# Power.net
KiCad netlist of a schematic drawn in Altium Designer
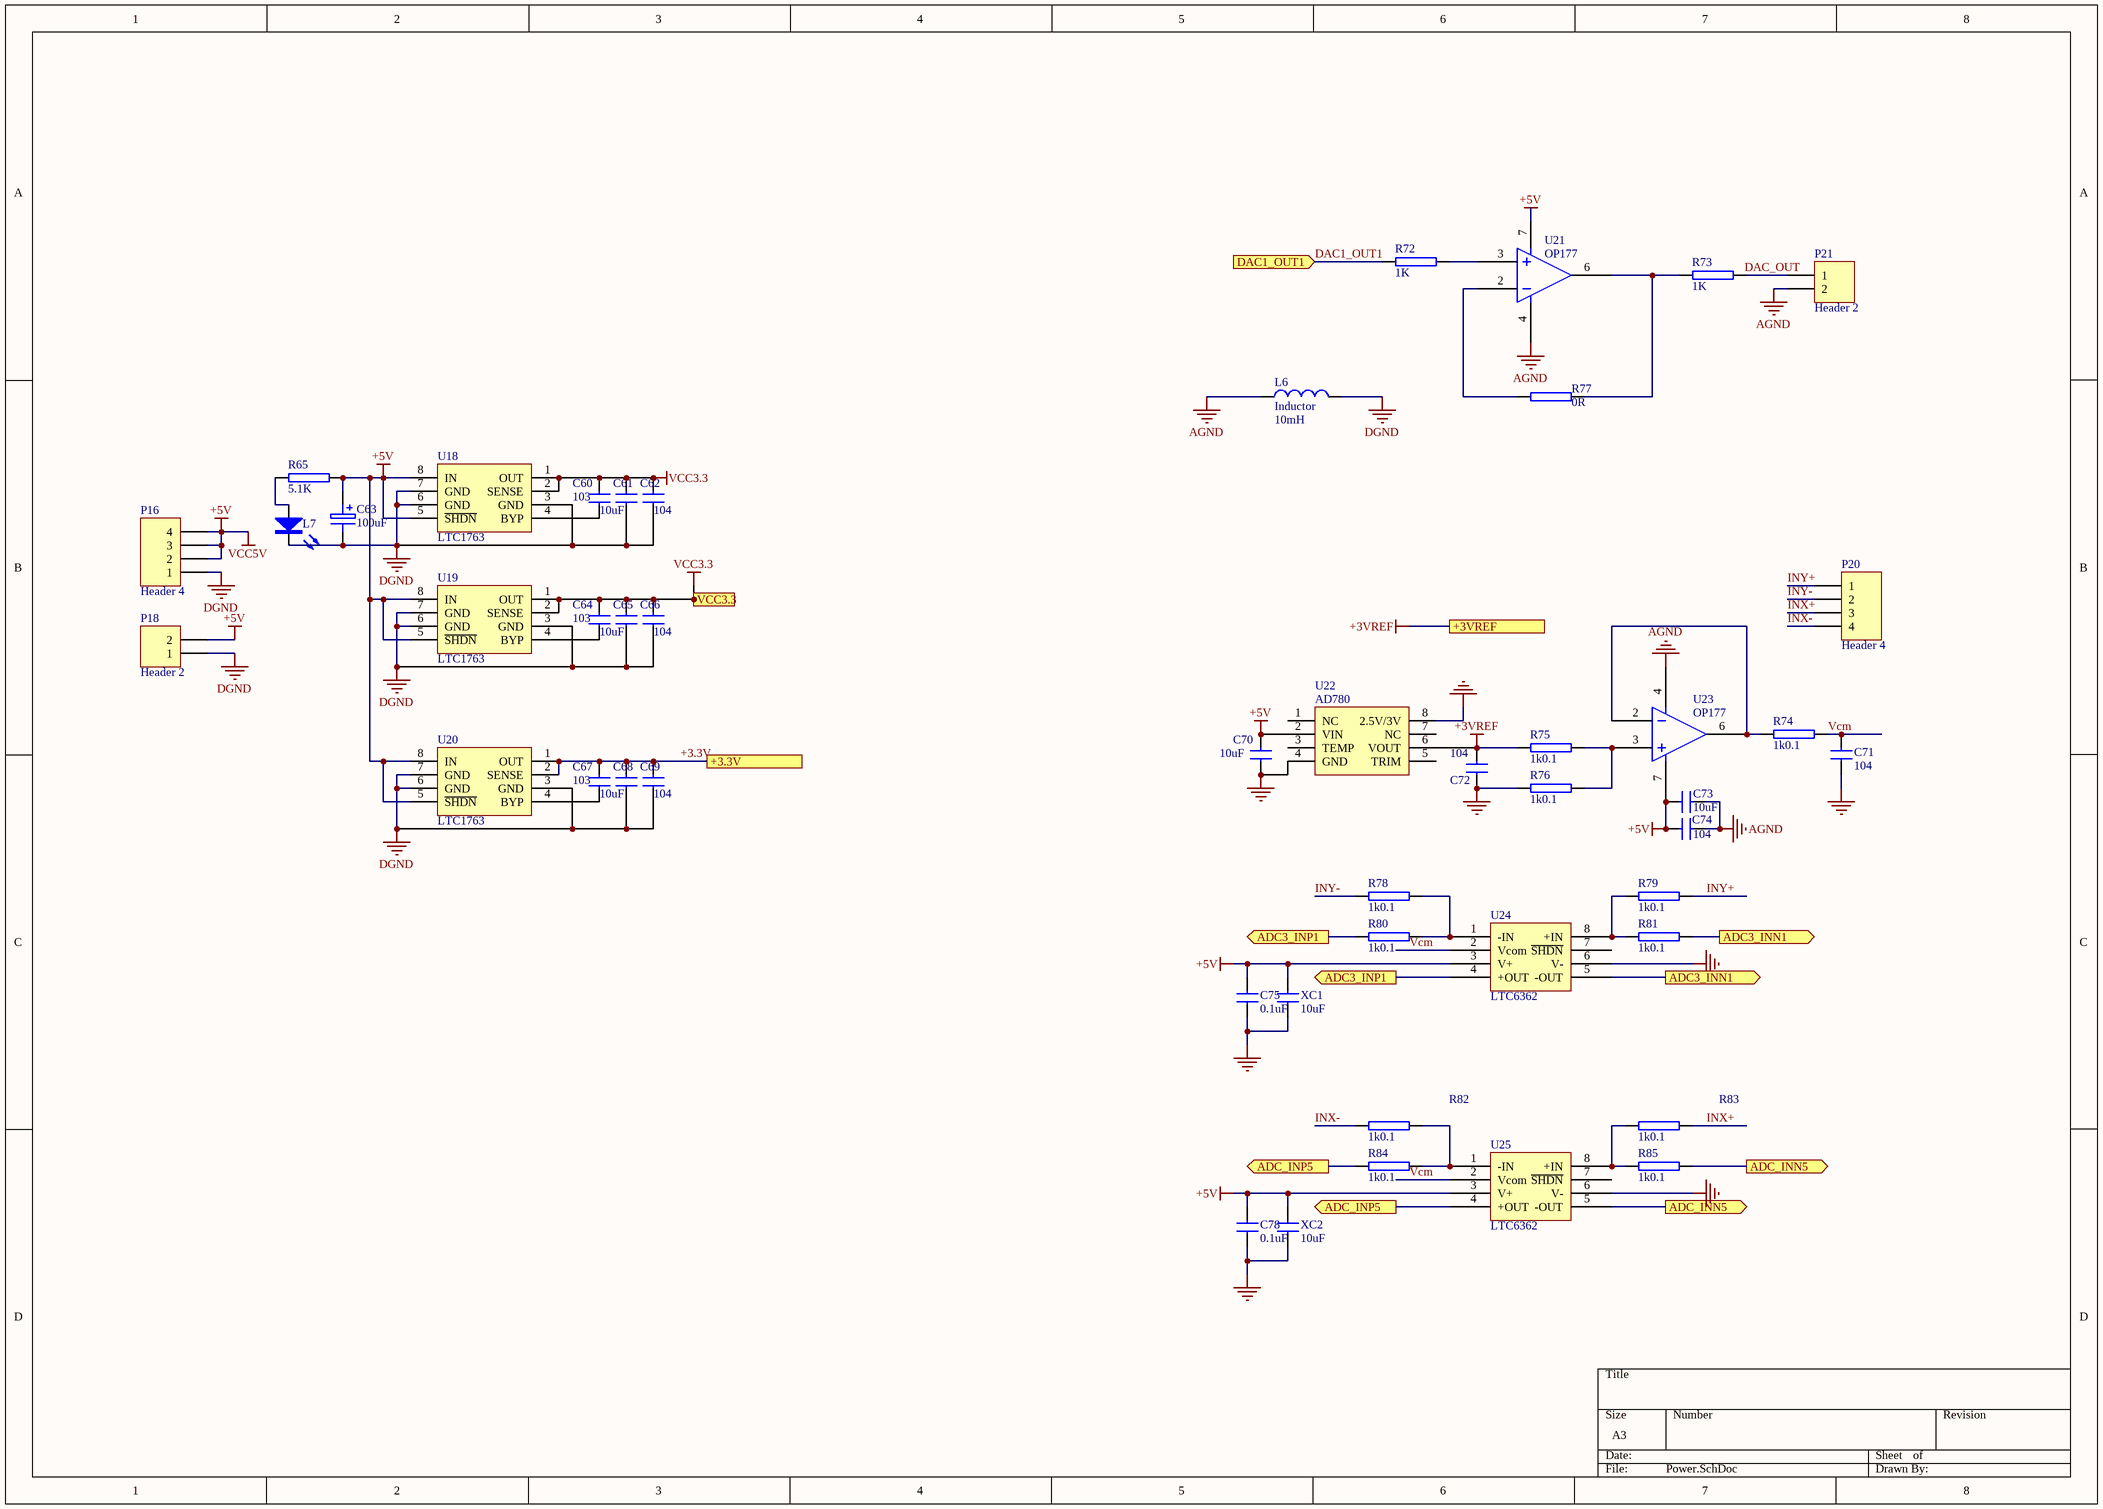
[diagram p0: Power.SchDoc]

(export (version "E")
  (design (tool "Eeschema 10.0.6"))
  (components
    (comp (ref "C60") (value "103") (footprint "0603") (libsource (lib "电容") (part "C")))
    (comp (ref "C61") (value "10uF") (footprint "0603") (libsource (lib "电容") (part "C")))
    (comp (ref "C62") (value "104") (footprint "0603") (libsource (lib "电容") (part "C")))
    (comp (ref "C63") (value "100uF") (footprint "100UF/25V_CA") (libsource (lib "电容") (part "ELECTRO1")))
    (comp (ref "C64") (value "103") (footprint "0603") (libsource (lib "电容") (part "C")))
    (comp (ref "C65") (value "10uF") (footprint "0603") (libsource (lib "电容") (part "C")))
    (comp (ref "C66") (value "104") (footprint "0603") (libsource (lib "电容") (part "C")))
    (comp (ref "C67") (value "103") (footprint "0603") (libsource (lib "电容") (part "C")))
    (comp (ref "C68") (value "10uF") (footprint "0603") (libsource (lib "电容") (part "C")))
    (comp (ref "C69") (value "104") (footprint "0603") (libsource (lib "电容") (part "C")))
    (comp (ref "C70") (value "10uF") (footprint "0603") (libsource (lib "*") (part "C")))
    (comp (ref "C71") (value "104") (footprint "0603") (libsource (lib "电容") (part "C")))
    (comp (ref "C72") (value "104") (footprint "0603") (libsource (lib "*") (part "C")))
    (comp (ref "C73") (value "10uF") (footprint "0603") (libsource (lib "电容") (part "C")))
    (comp (ref "C74") (value "104") (footprint "0603") (libsource (lib "电容") (part "C")))
    (comp (ref "C75") (value "0.1uF") (footprint "0603") (libsource (lib "电容") (part "C")))
    (comp (ref "C78") (value "0.1uF") (footprint "0603") (libsource (lib "电容") (part "C")))
    (comp (ref "L6")
      (value "Inductor")
      (footprint "0805")
      (fields (field (name "ALTIUM_VALUE") "10mH") (field (name "PUBLISHER") "Altium Limited"))
      (libsource (lib "Miscellaneous Devices") (part "Inductor"))
    )
    (comp (ref "L7") (value "LED") (footprint "0805LED") (libsource (lib "二极管") (part "LED")))
    (comp (ref "P16")
      (value "Header 4")
      (footprint "HDR1X4")
      (description "Header, 4-Pin")
      (fields (field (name "PUBLISHER") "Altium Limited"))
      (libsource (lib "") (part "Header 4_1"))
    )
    (comp (ref "P18")
      (value "Header 2")
      (footprint "HDR1X2")
      (description "Header, 2-Pin")
      (fields (field (name "PUBLISHER") "Altium Limited"))
      (libsource (lib "") (part "Header 2_1"))
    )
    (comp (ref "P20")
      (value "Header 4")
      (footprint "HDR1X4")
      (description "Header, 4-Pin")
      (fields (field (name "PUBLISHER") "Altium Limited"))
      (libsource (lib "Miscellaneous Connectors") (part "Header 4"))
    )
    (comp (ref "P21")
      (value "Header 2")
      (footprint "HDR1X2")
      (description "Header, 2-Pin")
      (fields (field (name "PUBLISHER") "Altium Limited"))
      (libsource (lib "Miscellaneous Connectors") (part "Header 2"))
    )
    (comp (ref "R65") (value "5.1K") (footprint "0603") (libsource (lib "电阻") (part "RES")))
    (comp (ref "R72") (value "1K") (footprint "0603") (libsource (lib "电阻") (part "RES")))
    (comp (ref "R73") (value "1K") (footprint "0603") (libsource (lib "电阻") (part "RES")))
    (comp (ref "R74") (value "1k0.1") (footprint "0603") (libsource (lib "电阻") (part "RES")))
    (comp (ref "R75") (value "1k0.1") (footprint "0603") (libsource (lib "电阻") (part "RES")))
    (comp (ref "R76") (value "1k0.1") (footprint "0603") (libsource (lib "电阻") (part "RES")))
    (comp (ref "R77") (value "0R") (footprint "0603") (libsource (lib "电阻") (part "RES")))
    (comp (ref "R78") (value "1k0.1") (footprint "0603") (libsource (lib "电阻") (part "RES")))
    (comp (ref "R79") (value "1k0.1") (footprint "0603") (libsource (lib "电阻") (part "RES")))
    (comp (ref "R80") (value "1k0.1") (footprint "0603") (libsource (lib "电阻") (part "RES")))
    (comp (ref "R81") (value "1k0.1") (footprint "0603") (libsource (lib "电阻") (part "RES")))
    (comp (ref "R82") (value "1k0.1") (footprint "0603") (libsource (lib "电阻") (part "RES")))
    (comp (ref "R83") (value "1k0.1") (footprint "0603") (libsource (lib "电阻") (part "RES")))
    (comp (ref "R84") (value "1k0.1") (footprint "0603") (libsource (lib "电阻") (part "RES")))
    (comp (ref "R85") (value "1k0.1") (footprint "0603") (libsource (lib "电阻") (part "RES")))
    (comp (ref "U18") (value "LTC1763") (footprint "SO-8") (libsource (lib "单片机") (part "LT1763")))
    (comp (ref "U19") (value "LTC1763") (footprint "SO-8") (libsource (lib "单片机") (part "LT1763")))
    (comp (ref "U20") (value "LTC1763") (footprint "SO-8") (libsource (lib "单片机") (part "LT1763")))
    (comp (ref "U21") (value "OP177") (footprint "SO-8") (libsource (lib "*") (part "LM207")))
    (comp (ref "U22") (value "AD780") (footprint "SO-8") (libsource (lib "*") (part "AD780")))
    (comp (ref "U23") (value "OP177") (footprint "SO-8") (libsource (lib "*") (part "LM207")))
    (comp (ref "U24")
      (value "LTC6362")
      (footprint "LT6350XIN")
      (description "SAR ADC Drive")
      (libsource (lib "ADorADC") (part "LTC6362"))
    )
    (comp (ref "U25")
      (value "LTC6362")
      (footprint "LT6350XIN")
      (description "SAR ADC Drive")
      (libsource (lib "ADorADC") (part "LTC6362"))
    )
    (comp (ref "XC1") (value "10uF") (footprint "0603") (libsource (lib "电容") (part "C")))
    (comp (ref "XC2") (value "10uF") (footprint "0603") (libsource (lib "电容") (part "C")))
  )
  (nets
    (net (code "1") (name "+3VREF") (class "Default")
      (node (ref "C72") (pin "2") (pinfunction "2_2") (pintype "passive"))
      (node (ref "R75") (pin "1") (pinfunction "1_1") (pintype "passive"))
      (node (ref "U22") (pin "6") (pinfunction "VOUT_6") (pintype "passive"))
    )
    (net (code "2") (name "+5V") (class "Default")
      (node (ref "C63") (pin "1") (pintype "passive"))
      (node (ref "C70") (pin "1") (pinfunction "1_1") (pintype "passive"))
      (node (ref "C73") (pin "2") (pinfunction "2_2") (pintype "passive"))
      (node (ref "C74") (pin "2") (pinfunction "2_2") (pintype "passive"))
      (node (ref "C75") (pin "2") (pinfunction "2_2") (pintype "passive"))
      (node (ref "C78") (pin "2") (pinfunction "2_2") (pintype "passive"))
      (node (ref "P16") (pin "2") (pinfunction "2_2") (pintype "passive"))
      (node (ref "P16") (pin "3") (pinfunction "3_3") (pintype "passive"))
      (node (ref "P16") (pin "4") (pinfunction "4_4") (pintype "passive"))
      (node (ref "P18") (pin "2") (pinfunction "2_2") (pintype "passive"))
      (node (ref "R65") (pin "1") (pinfunction "1_1") (pintype "passive"))
      (node (ref "U18") (pin "5") (pinfunction "~{SHDN}_5") (pintype "passive"))
      (node (ref "U18") (pin "8") (pinfunction "IN_8") (pintype "passive"))
      (node (ref "U19") (pin "5") (pinfunction "~{SHDN}_5") (pintype "passive"))
      (node (ref "U19") (pin "8") (pinfunction "IN_8") (pintype "passive"))
      (node (ref "U20") (pin "5") (pinfunction "~{SHDN}_5") (pintype "passive"))
      (node (ref "U20") (pin "8") (pinfunction "IN_8") (pintype "passive"))
      (node (ref "U21") (pin "7") (pintype "passive"))
      (node (ref "U22") (pin "2") (pinfunction "VIN_2") (pintype "passive"))
      (node (ref "U23") (pin "7") (pintype "passive"))
      (node (ref "U24") (pin "3") (pinfunction "V+_3") (pintype "passive"))
      (node (ref "U25") (pin "3") (pinfunction "V+_3") (pintype "passive"))
      (node (ref "XC1") (pin "1") (pinfunction "1_1") (pintype "passive"))
      (node (ref "XC2") (pin "1") (pinfunction "1_1") (pintype "passive"))
    )
    (net (code "3") (name "/+3.3V") (class "Default")
      (node (ref "C67") (pin "1") (pinfunction "1_1") (pintype "passive"))
      (node (ref "C68") (pin "1") (pinfunction "1_1") (pintype "passive"))
      (node (ref "C69") (pin "1") (pinfunction "1_1") (pintype "passive"))
      (node (ref "U20") (pin "1") (pinfunction "OUT_1") (pintype "passive"))
      (node (ref "U20") (pin "2") (pinfunction "SENSE_2") (pintype "passive"))
    )
    (net (code "4") (name "/ADC3_INN1") (class "Default")
      (node (ref "R81") (pin "2") (pinfunction "2_2") (pintype "passive"))
      (node (ref "U24") (pin "5") (pinfunction "-OUT_5") (pintype "passive"))
    )
    (net (code "5") (name "/ADC3_INP1") (class "Default")
      (node (ref "R80") (pin "1") (pinfunction "1_1") (pintype "passive"))
      (node (ref "U24") (pin "4") (pinfunction "+OUT_4") (pintype "passive"))
    )
    (net (code "6") (name "/ADC_INN5") (class "Default")
      (node (ref "R85") (pin "2") (pinfunction "2_2") (pintype "passive"))
      (node (ref "U25") (pin "5") (pinfunction "-OUT_5") (pintype "passive"))
    )
    (net (code "7") (name "/ADC_INP5") (class "Default")
      (node (ref "R84") (pin "1") (pinfunction "1_1") (pintype "passive"))
      (node (ref "U25") (pin "4") (pinfunction "+OUT_4") (pintype "passive"))
    )
    (net (code "8") (name "/DAC1_OUT1") (class "Default")
      (node (ref "R72") (pin "2") (pinfunction "2_2") (pintype "passive"))
    )
    (net (code "10") (name "/INX+") (class "Default")
      (node (ref "P20") (pin "3") (pinfunction "3_3") (pintype "passive"))
      (node (ref "R83") (pin "2") (pinfunction "2_2") (pintype "passive"))
    )
    (net (code "11") (name "/INX-") (class "Default")
      (node (ref "P20") (pin "4") (pinfunction "4_4") (pintype "passive"))
      (node (ref "R82") (pin "2") (pinfunction "2_2") (pintype "passive"))
    )
    (net (code "12") (name "/INY+") (class "Default")
      (node (ref "P20") (pin "1") (pinfunction "1_1") (pintype "passive"))
      (node (ref "R79") (pin "2") (pinfunction "2_2") (pintype "passive"))
    )
    (net (code "13") (name "/INY-") (class "Default")
      (node (ref "P20") (pin "2") (pinfunction "2_2") (pintype "passive"))
      (node (ref "R78") (pin "2") (pinfunction "2_2") (pintype "passive"))
    )
    (net (code "14") (name "/Vcm") (class "Default")
      (node (ref "C71") (pin "1") (pinfunction "1_1") (pintype "passive"))
      (node (ref "R74") (pin "2") (pinfunction "2_2") (pintype "passive"))
      (node (ref "U24") (pin "2") (pinfunction "Vcom_2") (pintype "passive"))
      (node (ref "U25") (pin "2") (pinfunction "Vcom_2") (pintype "passive"))
    )
    (net (code "15") (name "AGND") (class "Default")
      (node (ref "C70") (pin "2") (pinfunction "2_2") (pintype "passive"))
      (node (ref "C71") (pin "2") (pinfunction "2_2") (pintype "passive"))
      (node (ref "C72") (pin "1") (pinfunction "1_1") (pintype "passive"))
      (node (ref "C73") (pin "1") (pinfunction "1_1") (pintype "passive"))
      (node (ref "C74") (pin "1") (pinfunction "1_1") (pintype "passive"))
      (node (ref "C75") (pin "1") (pinfunction "1_1") (pintype "passive"))
      (node (ref "C78") (pin "1") (pinfunction "1_1") (pintype "passive"))
      (node (ref "L6") (pin "1") (pinfunction "1_1") (pintype "passive"))
      (node (ref "P21") (pin "2") (pinfunction "2_2") (pintype "passive"))
      (node (ref "R76") (pin "1") (pinfunction "1_1") (pintype "passive"))
      (node (ref "U21") (pin "4") (pintype "passive"))
      (node (ref "U22") (pin "4") (pinfunction "GND_4") (pintype "passive"))
      (node (ref "U22") (pin "8") (pinfunction "2.5V/3V_8") (pintype "passive"))
      (node (ref "U23") (pin "4") (pintype "passive"))
      (node (ref "U24") (pin "6") (pinfunction "V-_6") (pintype "passive"))
      (node (ref "U25") (pin "6") (pinfunction "V-_6") (pintype "passive"))
      (node (ref "XC1") (pin "2") (pinfunction "2_2") (pintype "passive"))
      (node (ref "XC2") (pin "2") (pinfunction "2_2") (pintype "passive"))
    )
    (net (code "16") (name "DGND") (class "Default")
      (node (ref "C61") (pin "2") (pinfunction "2_2") (pintype "passive"))
      (node (ref "C62") (pin "2") (pinfunction "2_2") (pintype "passive"))
      (node (ref "C63") (pin "2") (pintype "passive"))
      (node (ref "C65") (pin "2") (pinfunction "2_2") (pintype "passive"))
      (node (ref "C66") (pin "2") (pinfunction "2_2") (pintype "passive"))
      (node (ref "C68") (pin "2") (pinfunction "2_2") (pintype "passive"))
      (node (ref "C69") (pin "2") (pinfunction "2_2") (pintype "passive"))
      (node (ref "L6") (pin "2") (pinfunction "2_2") (pintype "passive"))
      (node (ref "L7") (pin "2") (pinfunction "K_2") (pintype "passive"))
      (node (ref "P16") (pin "1") (pinfunction "1_1") (pintype "passive"))
      (node (ref "P18") (pin "1") (pinfunction "1_1") (pintype "passive"))
      (node (ref "U18") (pin "3") (pinfunction "GND_3") (pintype "passive"))
      (node (ref "U18") (pin "6") (pinfunction "GND_6") (pintype "passive"))
      (node (ref "U18") (pin "7") (pinfunction "GND_7") (pintype "passive"))
      (node (ref "U19") (pin "3") (pinfunction "GND_3") (pintype "passive"))
      (node (ref "U19") (pin "6") (pinfunction "GND_6") (pintype "passive"))
      (node (ref "U19") (pin "7") (pinfunction "GND_7") (pintype "passive"))
      (node (ref "U20") (pin "3") (pinfunction "GND_3") (pintype "passive"))
      (node (ref "U20") (pin "6") (pinfunction "GND_6") (pintype "passive"))
      (node (ref "U20") (pin "7") (pinfunction "GND_7") (pintype "passive"))
    )
    (net (code "17") (name "Net-(L7-A)") (class "Default")
      (node (ref "L7") (pin "1") (pinfunction "A_1") (pintype "passive"))
      (node (ref "R65") (pin "2") (pinfunction "2_2") (pintype "passive"))
    )
    (net (code "18") (name "Net-(P21-Pad1)") (class "Default")
      (node (ref "P21") (pin "1") (pinfunction "1_1") (pintype "passive"))
      (node (ref "R73") (pin "1") (pinfunction "1_1") (pintype "passive"))
    )
    (net (code "19") (name "Net-(R72-Pad1)") (class "Default")
      (node (ref "R72") (pin "1") (pinfunction "1_1") (pintype "passive"))
      (node (ref "U21") (pin "3") (pintype "passive"))
    )
    (net (code "20") (name "Net-(R73-Pad2)") (class "Default")
      (node (ref "R73") (pin "2") (pinfunction "2_2") (pintype "passive"))
      (node (ref "R77") (pin "1") (pinfunction "1_1") (pintype "passive"))
      (node (ref "U21") (pin "6") (pintype "passive"))
    )
    (net (code "21") (name "Net-(R74-Pad1)") (class "Default")
      (node (ref "R74") (pin "1") (pinfunction "1_1") (pintype "passive"))
      (node (ref "U23") (pin "2") (pintype "passive"))
      (node (ref "U23") (pin "6") (pintype "passive"))
    )
    (net (code "22") (name "Net-(R75-Pad2)") (class "Default")
      (node (ref "R75") (pin "2") (pinfunction "2_2") (pintype "passive"))
      (node (ref "R76") (pin "2") (pinfunction "2_2") (pintype "passive"))
      (node (ref "U23") (pin "3") (pintype "passive"))
    )
    (net (code "23") (name "Net-(R77-Pad2)") (class "Default")
      (node (ref "R77") (pin "2") (pinfunction "2_2") (pintype "passive"))
      (node (ref "U21") (pin "2") (pintype "passive"))
    )
    (net (code "24") (name "Net-(U18-BYP)") (class "Default")
      (node (ref "C60") (pin "2") (pinfunction "2_2") (pintype "passive"))
      (node (ref "U18") (pin "4") (pinfunction "BYP_4") (pintype "passive"))
    )
    (net (code "25") (name "Net-(U19-BYP)") (class "Default")
      (node (ref "C64") (pin "2") (pinfunction "2_2") (pintype "passive"))
      (node (ref "U19") (pin "4") (pinfunction "BYP_4") (pintype "passive"))
    )
    (net (code "26") (name "Net-(U20-BYP)") (class "Default")
      (node (ref "C67") (pin "2") (pinfunction "2_2") (pintype "passive"))
      (node (ref "U20") (pin "4") (pinfunction "BYP_4") (pintype "passive"))
    )
    (net (code "27") (name "Net-(U24-+IN)") (class "Default")
      (node (ref "R79") (pin "1") (pinfunction "1_1") (pintype "passive"))
      (node (ref "R81") (pin "1") (pinfunction "1_1") (pintype "passive"))
      (node (ref "U24") (pin "8") (pinfunction "+IN_8") (pintype "passive"))
    )
    (net (code "28") (name "Net-(U24--IN)") (class "Default")
      (node (ref "R78") (pin "1") (pinfunction "1_1") (pintype "passive"))
      (node (ref "R80") (pin "2") (pinfunction "2_2") (pintype "passive"))
      (node (ref "U24") (pin "1") (pinfunction "-IN_1") (pintype "passive"))
    )
    (net (code "29") (name "Net-(U25-+IN)") (class "Default")
      (node (ref "R83") (pin "1") (pinfunction "1_1") (pintype "passive"))
      (node (ref "R85") (pin "1") (pinfunction "1_1") (pintype "passive"))
      (node (ref "U25") (pin "8") (pinfunction "+IN_8") (pintype "passive"))
    )
    (net (code "30") (name "Net-(U25--IN)") (class "Default")
      (node (ref "R82") (pin "1") (pinfunction "1_1") (pintype "passive"))
      (node (ref "R84") (pin "2") (pinfunction "2_2") (pintype "passive"))
      (node (ref "U25") (pin "1") (pinfunction "-IN_1") (pintype "passive"))
    )
    (net (code "31") (name "VCC3.3") (class "Default")
      (node (ref "C60") (pin "1") (pinfunction "1_1") (pintype "passive"))
      (node (ref "C61") (pin "1") (pinfunction "1_1") (pintype "passive"))
      (node (ref "C62") (pin "1") (pinfunction "1_1") (pintype "passive"))
      (node (ref "C64") (pin "1") (pinfunction "1_1") (pintype "passive"))
      (node (ref "C65") (pin "1") (pinfunction "1_1") (pintype "passive"))
      (node (ref "C66") (pin "1") (pinfunction "1_1") (pintype "passive"))
      (node (ref "U18") (pin "1") (pinfunction "OUT_1") (pintype "passive"))
      (node (ref "U18") (pin "2") (pinfunction "SENSE_2") (pintype "passive"))
      (node (ref "U19") (pin "1") (pinfunction "OUT_1") (pintype "passive"))
      (node (ref "U19") (pin "2") (pinfunction "SENSE_2") (pintype "passive"))
    )
    (net (code "32") (name "unconnected-(U22-NC-Pad1)") (class "Default")
      (node (ref "U22") (pin "1") (pinfunction "NC_1") (pintype "passive"))
    )
    (net (code "33") (name "unconnected-(U22-NC-Pad7)") (class "Default")
      (node (ref "U22") (pin "7") (pinfunction "NC_7") (pintype "passive"))
    )
    (net (code "34") (name "unconnected-(U22-TEMP-Pad3)") (class "Default")
      (node (ref "U22") (pin "3") (pinfunction "TEMP_3") (pintype "passive"))
    )
    (net (code "35") (name "unconnected-(U22-TRIM-Pad5)") (class "Default")
      (node (ref "U22") (pin "5") (pinfunction "TRIM_5") (pintype "passive"))
    )
    (net (code "36") (name "unconnected-(U24-~{SHDN}-Pad7)") (class "Default")
      (node (ref "U24") (pin "7") (pinfunction "~{SHDN}_7") (pintype "passive"))
    )
    (net (code "37") (name "unconnected-(U25-~{SHDN}-Pad7)") (class "Default")
      (node (ref "U25") (pin "7") (pinfunction "~{SHDN}_7") (pintype "passive"))
    )
  )
)
